# Toy.net
KiCad netlist of a schematic drawn in EAGLE
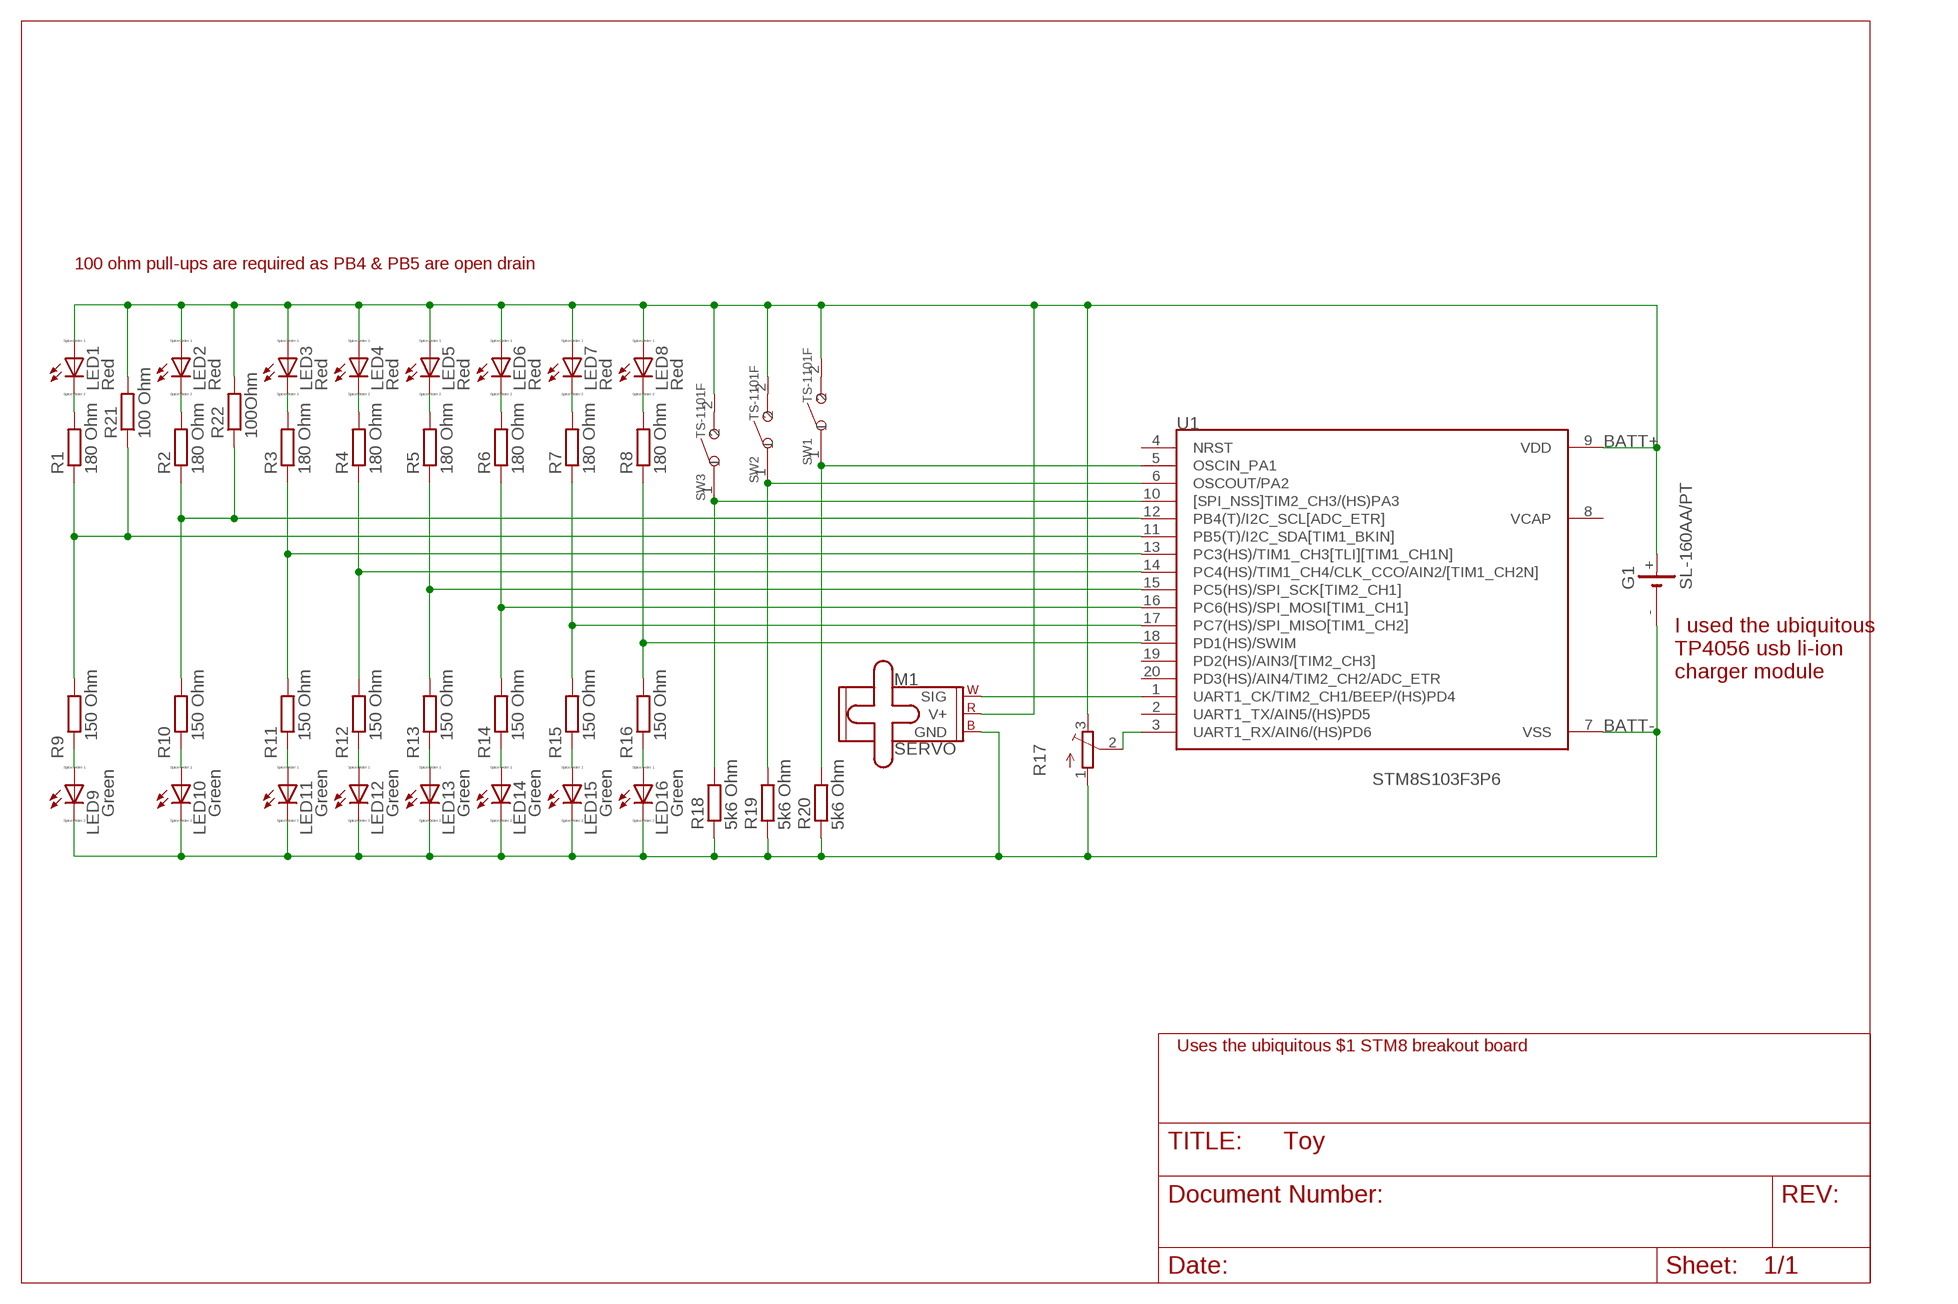
[diagram p0: schematic, sheet 1]

(export (version "E")
  (design (tool "Eeschema 10.0.6"))
  (components
    (comp (ref "G1")
      (value "SL-160AA/PT")
      (footprint "eagle-import:SL-160AA_PT")
      (libsource (lib "eagle-import") (part "SL-160AA/PT"))
    )
    (comp (ref "LED1")
      (value "Red")
      (footprint "eagle-import:LED_LD260")
      (libsource (lib "eagle-import") (part "LED_ELD260"))
    )
    (comp (ref "LED2")
      (value "Red")
      (footprint "eagle-import:LED_LD260")
      (libsource (lib "eagle-import") (part "LED_ELD260"))
    )
    (comp (ref "LED3")
      (value "Red")
      (footprint "eagle-import:LED_LD260")
      (libsource (lib "eagle-import") (part "LED_ELD260"))
    )
    (comp (ref "LED4")
      (value "Red")
      (footprint "eagle-import:LED_LD260")
      (libsource (lib "eagle-import") (part "LED_ELD260"))
    )
    (comp (ref "LED5")
      (value "Red")
      (footprint "eagle-import:LED_LD260")
      (libsource (lib "eagle-import") (part "LED_ELD260"))
    )
    (comp (ref "LED6")
      (value "Red")
      (footprint "eagle-import:LED_LD260")
      (libsource (lib "eagle-import") (part "LED_ELD260"))
    )
    (comp (ref "LED7")
      (value "Red")
      (footprint "eagle-import:LED_LD260")
      (libsource (lib "eagle-import") (part "LED_ELD260"))
    )
    (comp (ref "LED8")
      (value "Red")
      (footprint "eagle-import:LED_LD260")
      (libsource (lib "eagle-import") (part "LED_ELD260"))
    )
    (comp (ref "LED9")
      (value "Green")
      (footprint "eagle-import:LED_LD260")
      (libsource (lib "eagle-import") (part "LED_ELD260"))
    )
    (comp (ref "LED10")
      (value "Green")
      (footprint "eagle-import:LED_LD260")
      (libsource (lib "eagle-import") (part "LED_ELD260"))
    )
    (comp (ref "LED11")
      (value "Green")
      (footprint "eagle-import:LED_LD260")
      (libsource (lib "eagle-import") (part "LED_ELD260"))
    )
    (comp (ref "LED12")
      (value "Green")
      (footprint "eagle-import:LED_LD260")
      (libsource (lib "eagle-import") (part "LED_ELD260"))
    )
    (comp (ref "LED13")
      (value "Green")
      (footprint "eagle-import:LED_LD260")
      (libsource (lib "eagle-import") (part "LED_ELD260"))
    )
    (comp (ref "LED14")
      (value "Green")
      (footprint "eagle-import:LED_LD260")
      (libsource (lib "eagle-import") (part "LED_ELD260"))
    )
    (comp (ref "LED15")
      (value "Green")
      (footprint "eagle-import:LED_LD260")
      (libsource (lib "eagle-import") (part "LED_ELD260"))
    )
    (comp (ref "LED16")
      (value "Green")
      (footprint "eagle-import:LED_LD260")
      (libsource (lib "eagle-import") (part "LED_ELD260"))
    )
    (comp (ref "M1")
      (value "SERVO")
      (footprint "eagle-import:1X03")
      (libsource (lib "eagle-import") (part "SERVO"))
    )
    (comp (ref "R1")
      (value "180 Ohm")
      (footprint "eagle-import:0204_7")
      (libsource (lib "eagle-import") (part "R-EU_0204/7"))
    )
    (comp (ref "R2")
      (value "180 Ohm")
      (footprint "eagle-import:0204_7")
      (libsource (lib "eagle-import") (part "R-EU_0204/7"))
    )
    (comp (ref "R3")
      (value "180 Ohm")
      (footprint "eagle-import:0204_7")
      (libsource (lib "eagle-import") (part "R-EU_0204/7"))
    )
    (comp (ref "R4")
      (value "180 Ohm")
      (footprint "eagle-import:0204_7")
      (libsource (lib "eagle-import") (part "R-EU_0204/7"))
    )
    (comp (ref "R5")
      (value "180 Ohm")
      (footprint "eagle-import:0204_7")
      (libsource (lib "eagle-import") (part "R-EU_0204/7"))
    )
    (comp (ref "R6")
      (value "180 Ohm")
      (footprint "eagle-import:0204_7")
      (libsource (lib "eagle-import") (part "R-EU_0204/7"))
    )
    (comp (ref "R7")
      (value "180 Ohm")
      (footprint "eagle-import:0204_7")
      (libsource (lib "eagle-import") (part "R-EU_0204/7"))
    )
    (comp (ref "R8")
      (value "180 Ohm")
      (footprint "eagle-import:0204_7")
      (libsource (lib "eagle-import") (part "R-EU_0204/7"))
    )
    (comp (ref "R9")
      (value "150 Ohm")
      (footprint "eagle-import:0204_7")
      (libsource (lib "eagle-import") (part "R-EU_0204/7"))
    )
    (comp (ref "R10")
      (value "150 Ohm")
      (footprint "eagle-import:0204_7")
      (libsource (lib "eagle-import") (part "R-EU_0204/7"))
    )
    (comp (ref "R11")
      (value "150 Ohm")
      (footprint "eagle-import:0204_7")
      (libsource (lib "eagle-import") (part "R-EU_0204/7"))
    )
    (comp (ref "R12")
      (value "150 Ohm")
      (footprint "eagle-import:0204_7")
      (libsource (lib "eagle-import") (part "R-EU_0204/7"))
    )
    (comp (ref "R13")
      (value "150 Ohm")
      (footprint "eagle-import:0204_7")
      (libsource (lib "eagle-import") (part "R-EU_0204/7"))
    )
    (comp (ref "R14")
      (value "150 Ohm")
      (footprint "eagle-import:0204_7")
      (libsource (lib "eagle-import") (part "R-EU_0204/7"))
    )
    (comp (ref "R15")
      (value "150 Ohm")
      (footprint "eagle-import:0204_7")
      (libsource (lib "eagle-import") (part "R-EU_0204/7"))
    )
    (comp (ref "R16")
      (value "150 Ohm")
      (footprint "eagle-import:0204_7")
      (libsource (lib "eagle-import") (part "R-EU_0204/7"))
    )
    (comp (ref "R17")
      (value "TRIM_EU-3223G")
      (footprint "eagle-import:3223G")
      (libsource (lib "eagle-import") (part "TRIM_EU-3223G"))
    )
    (comp (ref "R18")
      (value "5k6 Ohm")
      (footprint "eagle-import:0204_7")
      (libsource (lib "eagle-import") (part "R-EU_0204/7"))
    )
    (comp (ref "R19")
      (value "5k6 Ohm")
      (footprint "eagle-import:0204_7")
      (libsource (lib "eagle-import") (part "R-EU_0204/7"))
    )
    (comp (ref "R20")
      (value "5k6 Ohm")
      (footprint "eagle-import:0204_7")
      (libsource (lib "eagle-import") (part "R-EU_0204/7"))
    )
    (comp (ref "R21")
      (value "100 Ohm")
      (footprint "eagle-import:0204_7")
      (libsource (lib "eagle-import") (part "resistor_348_R-EU_0204/7"))
    )
    (comp (ref "R22")
      (value "100Ohm")
      (footprint "eagle-import:0204_7")
      (libsource (lib "eagle-import") (part "resistor_348_R-EU_0204/7"))
    )
    (comp (ref "SW1")
      (value "TS-1101F")
      (footprint "eagle-import:SW2-5.0-6.0X3.0X4.3MM")
      (libsource (lib "eagle-import") (part "DIP-BUTTON(2P-6.0X3.0X4.3MM)-TS-1101F"))
    )
    (comp (ref "SW2")
      (value "TS-1101F")
      (footprint "eagle-import:SW2-5.0-6.0X3.0X4.3MM")
      (libsource (lib "eagle-import") (part "DIP-BUTTON(2P-6.0X3.0X4.3MM)-TS-1101F"))
    )
    (comp (ref "SW3")
      (value "TS-1101F")
      (footprint "eagle-import:SW2-5.0-6.0X3.0X4.3MM")
      (libsource (lib "eagle-import") (part "DIP-BUTTON(2P-6.0X3.0X4.3MM)-TS-1101F"))
    )
    (comp (ref "U1")
      (value "STM8S103F3P6")
      (footprint "eagle-import:SOP65P640X120-20N")
      (fields (field (name "MF") "STMicroelectronics"))
      (libsource (lib "eagle-import") (part "STM8S103F3P6"))
    )
  )
  (nets
    (net (code "1") (name "/BATT+") (class "Default")
      (node (ref "G1") (pin "+") (pinfunction "+_+") (pintype "passive"))
      (node (ref "LED1") (pin "A") (pinfunction "A_A") (pintype "passive"))
      (node (ref "LED2") (pin "A") (pinfunction "A_A") (pintype "passive"))
      (node (ref "LED3") (pin "A") (pinfunction "A_A") (pintype "passive"))
      (node (ref "LED4") (pin "A") (pinfunction "A_A") (pintype "passive"))
      (node (ref "LED5") (pin "A") (pinfunction "A_A") (pintype "passive"))
      (node (ref "LED6") (pin "A") (pinfunction "A_A") (pintype "passive"))
      (node (ref "LED7") (pin "A") (pinfunction "A_A") (pintype "passive"))
      (node (ref "LED8") (pin "A") (pinfunction "A_A") (pintype "passive"))
      (node (ref "M1") (pin "2") (pinfunction "V+_2") (pintype "bidirectional"))
      (node (ref "R17") (pin "3") (pinfunction "E_3") (pintype "passive"))
      (node (ref "R21") (pin "2") (pinfunction "2_2") (pintype "passive"))
      (node (ref "R22") (pin "2") (pinfunction "2_2") (pintype "passive"))
      (node (ref "SW1") (pin "2") (pinfunction "2_2") (pintype "bidirectional"))
      (node (ref "SW2") (pin "2") (pinfunction "2_2") (pintype "bidirectional"))
      (node (ref "SW3") (pin "2") (pinfunction "2_2") (pintype "bidirectional"))
      (node (ref "U1") (pin "9") (pinfunction "VDD_9") (pintype "power_in"))
    )
    (net (code "2") (name "/BATT-") (class "Default")
      (node (ref "G1") (pin "-") (pinfunction "-_-") (pintype "passive"))
      (node (ref "LED10") (pin "K") (pinfunction "C_K") (pintype "passive"))
      (node (ref "LED11") (pin "K") (pinfunction "C_K") (pintype "passive"))
      (node (ref "LED12") (pin "K") (pinfunction "C_K") (pintype "passive"))
      (node (ref "LED13") (pin "K") (pinfunction "C_K") (pintype "passive"))
      (node (ref "LED14") (pin "K") (pinfunction "C_K") (pintype "passive"))
      (node (ref "LED15") (pin "K") (pinfunction "C_K") (pintype "passive"))
      (node (ref "LED16") (pin "K") (pinfunction "C_K") (pintype "passive"))
      (node (ref "LED9") (pin "K") (pinfunction "C_K") (pintype "passive"))
      (node (ref "M1") (pin "3") (pinfunction "GND_3") (pintype "bidirectional"))
      (node (ref "R17") (pin "1") (pinfunction "A_1") (pintype "passive"))
      (node (ref "R18") (pin "1") (pinfunction "1_1") (pintype "passive"))
      (node (ref "R19") (pin "1") (pinfunction "1_1") (pintype "passive"))
      (node (ref "R20") (pin "1") (pinfunction "1_1") (pintype "passive"))
      (node (ref "U1") (pin "7") (pinfunction "VSS_7") (pintype "power_in"))
    )
    (net (code "3") (name "Net-(LED1-C)") (class "Default")
      (node (ref "LED1") (pin "K") (pinfunction "C_K") (pintype "passive"))
      (node (ref "R1") (pin "2") (pinfunction "2_2") (pintype "passive"))
    )
    (net (code "4") (name "Net-(LED2-C)") (class "Default")
      (node (ref "LED2") (pin "K") (pinfunction "C_K") (pintype "passive"))
      (node (ref "R2") (pin "2") (pinfunction "2_2") (pintype "passive"))
    )
    (net (code "5") (name "Net-(LED3-C)") (class "Default")
      (node (ref "LED3") (pin "K") (pinfunction "C_K") (pintype "passive"))
      (node (ref "R3") (pin "2") (pinfunction "2_2") (pintype "passive"))
    )
    (net (code "6") (name "Net-(LED4-C)") (class "Default")
      (node (ref "LED4") (pin "K") (pinfunction "C_K") (pintype "passive"))
      (node (ref "R4") (pin "2") (pinfunction "2_2") (pintype "passive"))
    )
    (net (code "7") (name "Net-(LED5-C)") (class "Default")
      (node (ref "LED5") (pin "K") (pinfunction "C_K") (pintype "passive"))
      (node (ref "R5") (pin "2") (pinfunction "2_2") (pintype "passive"))
    )
    (net (code "8") (name "Net-(LED6-C)") (class "Default")
      (node (ref "LED6") (pin "K") (pinfunction "C_K") (pintype "passive"))
      (node (ref "R6") (pin "2") (pinfunction "2_2") (pintype "passive"))
    )
    (net (code "9") (name "Net-(LED7-C)") (class "Default")
      (node (ref "LED7") (pin "K") (pinfunction "C_K") (pintype "passive"))
      (node (ref "R7") (pin "2") (pinfunction "2_2") (pintype "passive"))
    )
    (net (code "10") (name "Net-(LED8-C)") (class "Default")
      (node (ref "LED8") (pin "K") (pinfunction "C_K") (pintype "passive"))
      (node (ref "R8") (pin "2") (pinfunction "2_2") (pintype "passive"))
    )
    (net (code "11") (name "Net-(LED9-PadA)") (class "Default")
      (node (ref "LED9") (pin "A") (pinfunction "A_A") (pintype "passive"))
      (node (ref "R9") (pin "1") (pinfunction "1_1") (pintype "passive"))
    )
    (net (code "12") (name "Net-(LED10-PadA)") (class "Default")
      (node (ref "LED10") (pin "A") (pinfunction "A_A") (pintype "passive"))
      (node (ref "R10") (pin "1") (pinfunction "1_1") (pintype "passive"))
    )
    (net (code "13") (name "Net-(LED11-PadA)") (class "Default")
      (node (ref "LED11") (pin "A") (pinfunction "A_A") (pintype "passive"))
      (node (ref "R11") (pin "1") (pinfunction "1_1") (pintype "passive"))
    )
    (net (code "14") (name "Net-(LED12-PadA)") (class "Default")
      (node (ref "LED12") (pin "A") (pinfunction "A_A") (pintype "passive"))
      (node (ref "R12") (pin "1") (pinfunction "1_1") (pintype "passive"))
    )
    (net (code "15") (name "Net-(LED13-PadA)") (class "Default")
      (node (ref "LED13") (pin "A") (pinfunction "A_A") (pintype "passive"))
      (node (ref "R13") (pin "1") (pinfunction "1_1") (pintype "passive"))
    )
    (net (code "16") (name "Net-(LED14-PadA)") (class "Default")
      (node (ref "LED14") (pin "A") (pinfunction "A_A") (pintype "passive"))
      (node (ref "R14") (pin "1") (pinfunction "1_1") (pintype "passive"))
    )
    (net (code "17") (name "Net-(LED15-PadA)") (class "Default")
      (node (ref "LED15") (pin "A") (pinfunction "A_A") (pintype "passive"))
      (node (ref "R15") (pin "1") (pinfunction "1_1") (pintype "passive"))
    )
    (net (code "18") (name "Net-(LED16-PadA)") (class "Default")
      (node (ref "LED16") (pin "A") (pinfunction "A_A") (pintype "passive"))
      (node (ref "R16") (pin "1") (pinfunction "1_1") (pintype "passive"))
    )
    (net (code "19") (name "Net-(M1-SIG)") (class "Default")
      (node (ref "M1") (pin "1") (pinfunction "SIG_1") (pintype "bidirectional"))
      (node (ref "U1") (pin "1") (pinfunction "UART1_CK/TIM2_CH1/BEEP/(HS)PD4_1") (pintype "bidirectional"))
    )
    (net (code "20") (name "Net-(R17-S)") (class "Default")
      (node (ref "R17") (pin "2") (pinfunction "S_2") (pintype "passive"))
      (node (ref "U1") (pin "3") (pinfunction "UART1_RX/AIN6/(HS)PD6_3") (pintype "bidirectional"))
    )
    (net (code "21") (name "Net-(U1-OSCIN_PA1)") (class "Default")
      (node (ref "R20") (pin "2") (pinfunction "2_2") (pintype "passive"))
      (node (ref "SW1") (pin "1") (pinfunction "1_1") (pintype "bidirectional"))
      (node (ref "U1") (pin "5") (pinfunction "OSCIN_PA1_5") (pintype "bidirectional"))
    )
    (net (code "22") (name "Net-(U1-OSCOUT{slash}PA2)") (class "Default")
      (node (ref "R19") (pin "2") (pinfunction "2_2") (pintype "passive"))
      (node (ref "SW2") (pin "1") (pinfunction "1_1") (pintype "bidirectional"))
      (node (ref "U1") (pin "6") (pinfunction "OSCOUT/PA2_6") (pintype "bidirectional"))
    )
    (net (code "23") (name "Net-(U1-PB4(T){slash}I2C_SCL[ADC_ETR])") (class "Default")
      (node (ref "R10") (pin "2") (pinfunction "2_2") (pintype "passive"))
      (node (ref "R2") (pin "1") (pinfunction "1_1") (pintype "passive"))
      (node (ref "R22") (pin "1") (pinfunction "1_1") (pintype "passive"))
      (node (ref "U1") (pin "12") (pinfunction "PB4(T)/I2C_SCL[ADC_ETR]_12") (pintype "bidirectional"))
    )
    (net (code "24") (name "Net-(U1-PB5(T){slash}I2C_SDA[TIM1_BKIN])") (class "Default")
      (node (ref "R1") (pin "1") (pinfunction "1_1") (pintype "passive"))
      (node (ref "R21") (pin "1") (pinfunction "1_1") (pintype "passive"))
      (node (ref "R9") (pin "2") (pinfunction "2_2") (pintype "passive"))
      (node (ref "U1") (pin "11") (pinfunction "PB5(T)/I2C_SDA[TIM1_BKIN]_11") (pintype "bidirectional"))
    )
    (net (code "25") (name "Net-(U1-PC3(HS){slash}TIM1_CH3[TLI][TIM1_CH1N])") (class "Default")
      (node (ref "R11") (pin "2") (pinfunction "2_2") (pintype "passive"))
      (node (ref "R3") (pin "1") (pinfunction "1_1") (pintype "passive"))
      (node (ref "U1") (pin "13") (pinfunction "PC3(HS)/TIM1_CH3[TLI][TIM1_CH1N]_13") (pintype "bidirectional"))
    )
    (net (code "26") (name "Net-(U1-PC4(HS){slash}TIM1_CH4{slash}CLK_CCO{slash}AIN2{slash}[TIM1_CH2N])") (class "Default")
      (node (ref "R12") (pin "2") (pinfunction "2_2") (pintype "passive"))
      (node (ref "R4") (pin "1") (pinfunction "1_1") (pintype "passive"))
      (node (ref "U1") (pin "14") (pinfunction "PC4(HS)/TIM1_CH4/CLK_CCO/AIN2/[TIM1_CH2N]_14") (pintype "bidirectional"))
    )
    (net (code "27") (name "Net-(U1-PC5(HS){slash}SPI_SCK[TIM2_CH1])") (class "Default")
      (node (ref "R13") (pin "2") (pinfunction "2_2") (pintype "passive"))
      (node (ref "R5") (pin "1") (pinfunction "1_1") (pintype "passive"))
      (node (ref "U1") (pin "15") (pinfunction "PC5(HS)/SPI_SCK[TIM2_CH1]_15") (pintype "bidirectional"))
    )
    (net (code "28") (name "Net-(U1-PC6(HS){slash}SPI_MOSI[TIM1_CH1])") (class "Default")
      (node (ref "R14") (pin "2") (pinfunction "2_2") (pintype "passive"))
      (node (ref "R6") (pin "1") (pinfunction "1_1") (pintype "passive"))
      (node (ref "U1") (pin "16") (pinfunction "PC6(HS)/SPI_MOSI[TIM1_CH1]_16") (pintype "bidirectional"))
    )
    (net (code "29") (name "Net-(U1-PC7(HS){slash}SPI_MISO[TIM1_CH2])") (class "Default")
      (node (ref "R15") (pin "2") (pinfunction "2_2") (pintype "passive"))
      (node (ref "R7") (pin "1") (pinfunction "1_1") (pintype "passive"))
      (node (ref "U1") (pin "17") (pinfunction "PC7(HS)/SPI_MISO[TIM1_CH2]_17") (pintype "bidirectional"))
    )
    (net (code "30") (name "Net-(U1-PD1(HS){slash}SWIM)") (class "Default")
      (node (ref "R16") (pin "2") (pinfunction "2_2") (pintype "passive"))
      (node (ref "R8") (pin "1") (pinfunction "1_1") (pintype "passive"))
      (node (ref "U1") (pin "18") (pinfunction "PD1(HS)/SWIM_18") (pintype "bidirectional"))
    )
    (net (code "31") (name "Net-(U1-[SPI_NSS]TIM2_CH3{slash}(HS)PA3)") (class "Default")
      (node (ref "R18") (pin "2") (pinfunction "2_2") (pintype "passive"))
      (node (ref "SW3") (pin "1") (pinfunction "1_1") (pintype "bidirectional"))
      (node (ref "U1") (pin "10") (pinfunction "[SPI_NSS]TIM2_CH3/(HS)PA3_10") (pintype "bidirectional"))
    )
    (net (code "32") (name "unconnected-(G1---Pad-@1)") (class "Default")
      (node (ref "G1") (pin "-@1") (pinfunction "-_-@1") (pintype "passive"))
    )
    (net (code "33") (name "unconnected-(U1-NRST-Pad4)") (class "Default")
      (node (ref "U1") (pin "4") (pinfunction "NRST_4") (pintype "bidirectional"))
    )
    (net (code "34") (name "unconnected-(U1-PD2(HS){slash}AIN3{slash}[TIM2_CH3]-Pad19)") (class "Default")
      (node (ref "U1") (pin "19") (pinfunction "PD2(HS)/AIN3/[TIM2_CH3]_19") (pintype "bidirectional"))
    )
    (net (code "35") (name "unconnected-(U1-PD3(HS){slash}AIN4{slash}TIM2_CH2{slash}ADC_ETR-Pad20)") (class "Default")
      (node (ref "U1") (pin "20") (pinfunction "PD3(HS)/AIN4/TIM2_CH2/ADC_ETR_20") (pintype "bidirectional"))
    )
    (net (code "36") (name "unconnected-(U1-UART1_TX{slash}AIN5{slash}(HS)PD5-Pad2)") (class "Default")
      (node (ref "U1") (pin "2") (pinfunction "UART1_TX/AIN5/(HS)PD5_2") (pintype "bidirectional"))
    )
    (net (code "37") (name "unconnected-(U1-VCAP-Pad8)") (class "Default")
      (node (ref "U1") (pin "8") (pinfunction "VCAP_8") (pintype "passive"))
    )
  )
)
